# pcb_univ_3-_1-3-5_-x-x-rev5.net
KiCad netlist of a schematic drawn in EAGLE
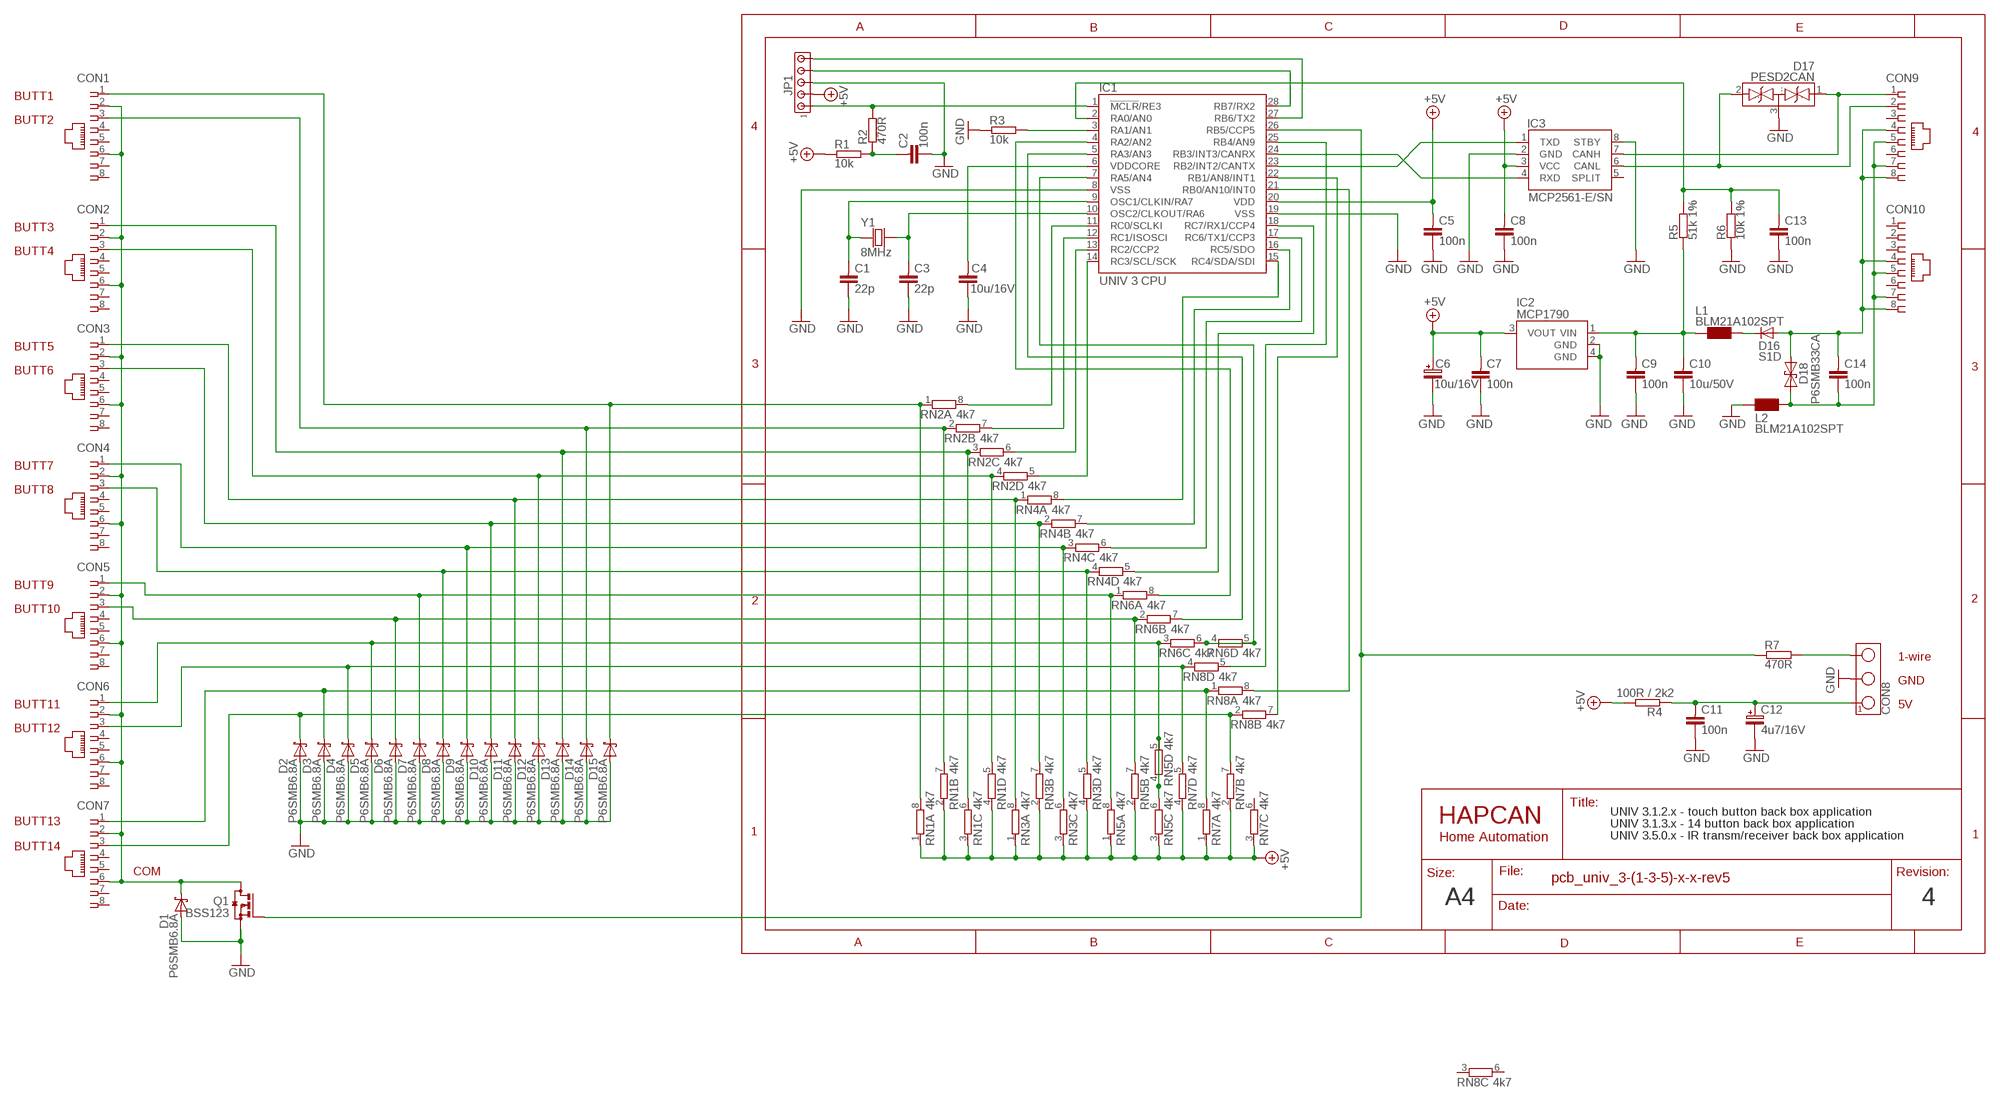
[diagram p0: schematic, sheet 1]

(export (version "E")
  (design (tool "Eeschema 10.0.6"))
  (components
    (comp (ref "C1")
      (value "22p")
      (footprint "eagle-import:0805")
      (libsource (lib "eagle-import") (part "CAPACITOR0805"))
    )
    (comp (ref "C2")
      (value "100n")
      (footprint "eagle-import:0805")
      (libsource (lib "eagle-import") (part "CAPACITOR0805"))
    )
    (comp (ref "C3")
      (value "22p")
      (footprint "eagle-import:0805")
      (libsource (lib "eagle-import") (part "CAPACITOR0805"))
    )
    (comp (ref "C4")
      (value "10u/16V")
      (footprint "eagle-import:0805")
      (libsource (lib "eagle-import") (part "CAPACITOR0805"))
    )
    (comp (ref "C5")
      (value "100n")
      (footprint "eagle-import:0805")
      (libsource (lib "eagle-import") (part "CAPACITOR0805"))
    )
    (comp (ref "C6")
      (value "10u/16V")
      (footprint "eagle-import:SMC_B")
      (libsource (lib "eagle-import") (part "CAPACITOR-POLARIZED-SMC_B"))
    )
    (comp (ref "C7")
      (value "100n")
      (footprint "eagle-import:0805")
      (libsource (lib "eagle-import") (part "CAPACITOR0805"))
    )
    (comp (ref "C8")
      (value "100n")
      (footprint "eagle-import:0805")
      (libsource (lib "eagle-import") (part "CAPACITOR0805"))
    )
    (comp (ref "C9")
      (value "100n")
      (footprint "eagle-import:0805")
      (libsource (lib "eagle-import") (part "CAPACITOR0805"))
    )
    (comp (ref "C10")
      (value "10u/50V")
      (footprint "eagle-import:1210")
      (libsource (lib "eagle-import") (part "CAPACITOR1210"))
    )
    (comp (ref "C11")
      (value "100n")
      (footprint "eagle-import:0805")
      (libsource (lib "eagle-import") (part "CAPACITOR0805"))
    )
    (comp (ref "C12")
      (value "4u7/16V")
      (footprint "eagle-import:SMC_B")
      (libsource (lib "eagle-import") (part "CAPACITOR-POLARIZED-SMC_B"))
    )
    (comp (ref "C13")
      (value "100n")
      (footprint "eagle-import:0805")
      (libsource (lib "eagle-import") (part "CAPACITOR0805"))
    )
    (comp (ref "C14")
      (value "100n")
      (footprint "eagle-import:0805")
      (libsource (lib "eagle-import") (part "CAPACITOR0805"))
    )
    (comp (ref "CON1")
      (value "RJ45-SOCKET")
      (footprint "eagle-import:RJ45-PCB-SOCKET")
      (libsource (lib "eagle-import") (part "RJ45-SOCKET"))
    )
    (comp (ref "CON2")
      (value "RJ45-SOCKET")
      (footprint "eagle-import:RJ45-PCB-SOCKET")
      (libsource (lib "eagle-import") (part "RJ45-SOCKET"))
    )
    (comp (ref "CON3")
      (value "RJ45-SOCKET")
      (footprint "eagle-import:RJ45-PCB-SOCKET")
      (libsource (lib "eagle-import") (part "RJ45-SOCKET"))
    )
    (comp (ref "CON4")
      (value "RJ45-SOCKET")
      (footprint "eagle-import:RJ45-PCB-SOCKET")
      (libsource (lib "eagle-import") (part "RJ45-SOCKET"))
    )
    (comp (ref "CON5")
      (value "RJ45-SOCKET")
      (footprint "eagle-import:RJ45-PCB-SOCKET")
      (libsource (lib "eagle-import") (part "RJ45-SOCKET"))
    )
    (comp (ref "CON6")
      (value "RJ45-SOCKET")
      (footprint "eagle-import:RJ45-PCB-SOCKET")
      (libsource (lib "eagle-import") (part "RJ45-SOCKET"))
    )
    (comp (ref "CON7")
      (value "RJ45-SOCKET")
      (footprint "eagle-import:RJ45-PCB-SOCKET")
      (libsource (lib "eagle-import") (part "RJ45-SOCKET"))
    )
    (comp (ref "CON8")
      (value "TERMINAL-3")
      (footprint "eagle-import:ARK3-5X10.5MM")
      (libsource (lib "eagle-import") (part "TERMINAL-3-5X10.5MM"))
    )
    (comp (ref "CON9")
      (value "RJ45-SOCKET")
      (footprint "eagle-import:RJ45-PCB-SOCKET")
      (libsource (lib "eagle-import") (part "RJ45-SOCKET"))
    )
    (comp (ref "CON10")
      (value "RJ45-SOCKET")
      (footprint "eagle-import:RJ45-PCB-SOCKET")
      (libsource (lib "eagle-import") (part "RJ45-SOCKET"))
    )
    (comp (ref "D1")
      (value "P6SMB6.8A")
      (footprint "eagle-import:DO-214")
      (libsource (lib "eagle-import") (part "DIODE_TRANSIL1_DO214"))
    )
    (comp (ref "D2")
      (value "P6SMB6.8A")
      (footprint "eagle-import:DO-214")
      (libsource (lib "eagle-import") (part "DIODE_TRANSIL1_DO214"))
    )
    (comp (ref "D3")
      (value "P6SMB6.8A")
      (footprint "eagle-import:DO-214")
      (libsource (lib "eagle-import") (part "DIODE_TRANSIL1_DO214"))
    )
    (comp (ref "D4")
      (value "P6SMB6.8A")
      (footprint "eagle-import:DO-214")
      (libsource (lib "eagle-import") (part "DIODE_TRANSIL1_DO214"))
    )
    (comp (ref "D5")
      (value "P6SMB6.8A")
      (footprint "eagle-import:DO-214")
      (libsource (lib "eagle-import") (part "DIODE_TRANSIL1_DO214"))
    )
    (comp (ref "D6")
      (value "P6SMB6.8A")
      (footprint "eagle-import:DO-214")
      (libsource (lib "eagle-import") (part "DIODE_TRANSIL1_DO214"))
    )
    (comp (ref "D7")
      (value "P6SMB6.8A")
      (footprint "eagle-import:DO-214")
      (libsource (lib "eagle-import") (part "DIODE_TRANSIL1_DO214"))
    )
    (comp (ref "D8")
      (value "P6SMB6.8A")
      (footprint "eagle-import:DO-214")
      (libsource (lib "eagle-import") (part "DIODE_TRANSIL1_DO214"))
    )
    (comp (ref "D9")
      (value "P6SMB6.8A")
      (footprint "eagle-import:DO-214")
      (libsource (lib "eagle-import") (part "DIODE_TRANSIL1_DO214"))
    )
    (comp (ref "D10")
      (value "P6SMB6.8A")
      (footprint "eagle-import:DO-214")
      (libsource (lib "eagle-import") (part "DIODE_TRANSIL1_DO214"))
    )
    (comp (ref "D11")
      (value "P6SMB6.8A")
      (footprint "eagle-import:DO-214")
      (libsource (lib "eagle-import") (part "DIODE_TRANSIL1_DO214"))
    )
    (comp (ref "D12")
      (value "P6SMB6.8A")
      (footprint "eagle-import:DO-214")
      (libsource (lib "eagle-import") (part "DIODE_TRANSIL1_DO214"))
    )
    (comp (ref "D13")
      (value "P6SMB6.8A")
      (footprint "eagle-import:DO-214")
      (libsource (lib "eagle-import") (part "DIODE_TRANSIL1_DO214"))
    )
    (comp (ref "D14")
      (value "P6SMB6.8A")
      (footprint "eagle-import:DO-214")
      (libsource (lib "eagle-import") (part "DIODE_TRANSIL1_DO214"))
    )
    (comp (ref "D15")
      (value "P6SMB6.8A")
      (footprint "eagle-import:DO-214")
      (libsource (lib "eagle-import") (part "DIODE_TRANSIL1_DO214"))
    )
    (comp (ref "D16")
      (value "S1D")
      (footprint "eagle-import:DO-214")
      (libsource (lib "eagle-import") (part "DIODE_DO-214"))
    )
    (comp (ref "D17")
      (value "PESD2CAN")
      (footprint "eagle-import:SOT-23")
      (libsource (lib "eagle-import") (part "PESD2CANSOT-23"))
    )
    (comp (ref "D18")
      (value "P6SMB33CA")
      (footprint "eagle-import:DO-214_TRANSIL2")
      (libsource (lib "eagle-import") (part "DIODE_TRANSIL2"))
    )
    (comp (ref "IC1")
      (value "UNIV 3 CPU")
      (footprint "eagle-import:UNIV3CPU")
      (libsource (lib "eagle-import") (part "UNIV3CPU-I/SO"))
    )
    (comp (ref "IC2")
      (value "MCP1790")
      (footprint "eagle-import:SOT-223")
      (libsource (lib "eagle-import") (part "MCP1790"))
    )
    (comp (ref "IC3")
      (value "MCP2561-E/SN")
      (footprint "eagle-import:SO-08")
      (libsource (lib "eagle-import") (part "MCP2561-E/SN"))
    )
    (comp (ref "JP1")
      (value "HEADER5")
      (footprint "eagle-import:SIP-5")
      (libsource (lib "eagle-import") (part "HEADER5"))
    )
    (comp (ref "L1")
      (value "BLM21A102SPT")
      (footprint "eagle-import:0805@1")
      (libsource (lib "eagle-import") (part "BLMXXX"))
    )
    (comp (ref "L2")
      (value "BLM21A102SPT")
      (footprint "eagle-import:0805@1")
      (libsource (lib "eagle-import") (part "BLMXXX"))
    )
    (comp (ref "Q1")
      (value "BSS123")
      (footprint "eagle-import:SOT23")
      (libsource (lib "eagle-import") (part "BSS123"))
    )
    (comp (ref "R1")
      (value "10k")
      (footprint "eagle-import:0805")
      (libsource (lib "eagle-import") (part "RESISTOR0805"))
    )
    (comp (ref "R2")
      (value "470R")
      (footprint "eagle-import:0805")
      (libsource (lib "eagle-import") (part "RESISTOR0805"))
    )
    (comp (ref "R3")
      (value "10k")
      (footprint "eagle-import:0805")
      (libsource (lib "eagle-import") (part "RESISTOR0805"))
    )
    (comp (ref "R4")
      (value "100R / 2k2")
      (footprint "eagle-import:0805")
      (libsource (lib "eagle-import") (part "RESISTOR0805"))
    )
    (comp (ref "R5")
      (value "51k 1%")
      (footprint "eagle-import:0805")
      (libsource (lib "eagle-import") (part "RESISTOR0805"))
    )
    (comp (ref "R6")
      (value "10k 1%")
      (footprint "eagle-import:0805")
      (libsource (lib "eagle-import") (part "RESISTOR0805"))
    )
    (comp (ref "R7")
      (value "470R")
      (footprint "eagle-import:0805")
      (libsource (lib "eagle-import") (part "RESISTOR0805"))
    )
    (comp (ref "RN1")
      (value "4k7")
      (footprint "eagle-import:EXB38V")
      (libsource (lib "eagle-import") (part "4R-NEXB38V"))
    )
    (comp (ref "RN2")
      (value "4k7")
      (footprint "eagle-import:EXB38V")
      (libsource (lib "eagle-import") (part "4R-NEXB38V"))
    )
    (comp (ref "RN3")
      (value "4k7")
      (footprint "eagle-import:EXB38V")
      (libsource (lib "eagle-import") (part "4R-NEXB38V"))
    )
    (comp (ref "RN4")
      (value "4k7")
      (footprint "eagle-import:EXB38V")
      (libsource (lib "eagle-import") (part "4R-NEXB38V"))
    )
    (comp (ref "RN5")
      (value "4k7")
      (footprint "eagle-import:EXB38V")
      (libsource (lib "eagle-import") (part "4R-NEXB38V"))
    )
    (comp (ref "RN6")
      (value "4k7")
      (footprint "eagle-import:EXB38V")
      (libsource (lib "eagle-import") (part "4R-NEXB38V"))
    )
    (comp (ref "RN7")
      (value "4k7")
      (footprint "eagle-import:EXB38V")
      (libsource (lib "eagle-import") (part "4R-NEXB38V"))
    )
    (comp (ref "RN8")
      (value "4k7")
      (footprint "eagle-import:EXB38V")
      (libsource (lib "eagle-import") (part "4R-NEXB38V"))
    )
    (comp (ref "Y1")
      (value "8MHz")
      (footprint "eagle-import:CRYSTAL-HC49V")
      (libsource (lib "eagle-import") (part "CRYSTAL-HC49V"))
    )
  )
  (nets
    (net (code "1") (name "+5V") (class "Default")
      (node (ref "C5") (pin "1") (pinfunction "1_1") (pintype "passive"))
      (node (ref "C6") (pin "+") (pinfunction "1_+") (pintype "passive"))
      (node (ref "C7") (pin "1") (pinfunction "1_1") (pintype "passive"))
      (node (ref "C8") (pin "1") (pinfunction "1_1") (pintype "passive"))
      (node (ref "IC1") (pin "20") (pinfunction "VDD_20") (pintype "bidirectional"))
      (node (ref "IC2") (pin "3") (pinfunction "VOUT_3") (pintype "bidirectional"))
      (node (ref "IC3") (pin "3") (pinfunction "VCC_3") (pintype "bidirectional"))
      (node (ref "JP1") (pin "2") (pinfunction "2_2") (pintype "passive"))
      (node (ref "R1") (pin "1") (pinfunction "1_1") (pintype "passive"))
      (node (ref "R4") (pin "1") (pinfunction "1_1") (pintype "passive"))
      (node (ref "RN1") (pin "1") (pinfunction "1_1") (pintype "passive"))
      (node (ref "RN1") (pin "2") (pinfunction "1_2") (pintype "passive"))
      (node (ref "RN1") (pin "3") (pinfunction "1_3") (pintype "passive"))
      (node (ref "RN1") (pin "4") (pinfunction "1_4") (pintype "passive"))
      (node (ref "RN3") (pin "1") (pinfunction "1_1") (pintype "passive"))
      (node (ref "RN3") (pin "2") (pinfunction "1_2") (pintype "passive"))
      (node (ref "RN3") (pin "3") (pinfunction "1_3") (pintype "passive"))
      (node (ref "RN3") (pin "4") (pinfunction "1_4") (pintype "passive"))
      (node (ref "RN5") (pin "1") (pinfunction "1_1") (pintype "passive"))
      (node (ref "RN5") (pin "2") (pinfunction "1_2") (pintype "passive"))
      (node (ref "RN5") (pin "3") (pinfunction "1_3") (pintype "passive"))
      (node (ref "RN7") (pin "1") (pinfunction "1_1") (pintype "passive"))
      (node (ref "RN7") (pin "2") (pinfunction "1_2") (pintype "passive"))
      (node (ref "RN7") (pin "3") (pinfunction "1_3") (pintype "passive"))
      (node (ref "RN7") (pin "4") (pinfunction "1_4") (pintype "passive"))
    )
    (net (code "2") (name "GND") (class "Default")
      (node (ref "C1") (pin "2") (pinfunction "2_2") (pintype "passive"))
      (node (ref "C10") (pin "2") (pinfunction "2_2") (pintype "passive"))
      (node (ref "C11") (pin "2") (pinfunction "2_2") (pintype "passive"))
      (node (ref "C12") (pin "-") (pinfunction "2_-") (pintype "passive"))
      (node (ref "C13") (pin "2") (pinfunction "2_2") (pintype "passive"))
      (node (ref "C2") (pin "2") (pinfunction "2_2") (pintype "passive"))
      (node (ref "C3") (pin "2") (pinfunction "2_2") (pintype "passive"))
      (node (ref "C4") (pin "2") (pinfunction "2_2") (pintype "passive"))
      (node (ref "C5") (pin "2") (pinfunction "2_2") (pintype "passive"))
      (node (ref "C6") (pin "-") (pinfunction "2_-") (pintype "passive"))
      (node (ref "C7") (pin "2") (pinfunction "2_2") (pintype "passive"))
      (node (ref "C8") (pin "2") (pinfunction "2_2") (pintype "passive"))
      (node (ref "C9") (pin "2") (pinfunction "2_2") (pintype "passive"))
      (node (ref "CON8") (pin "2") (pinfunction "2_2") (pintype "passive"))
      (node (ref "D1") (pin "A") (pinfunction "A_A") (pintype "passive"))
      (node (ref "D10") (pin "A") (pinfunction "A_A") (pintype "passive"))
      (node (ref "D11") (pin "A") (pinfunction "A_A") (pintype "passive"))
      (node (ref "D12") (pin "A") (pinfunction "A_A") (pintype "passive"))
      (node (ref "D13") (pin "A") (pinfunction "A_A") (pintype "passive"))
      (node (ref "D14") (pin "A") (pinfunction "A_A") (pintype "passive"))
      (node (ref "D15") (pin "A") (pinfunction "A_A") (pintype "passive"))
      (node (ref "D17") (pin "3") (pinfunction "..._3") (pintype "bidirectional"))
      (node (ref "D2") (pin "A") (pinfunction "A_A") (pintype "passive"))
      (node (ref "D3") (pin "A") (pinfunction "A_A") (pintype "passive"))
      (node (ref "D4") (pin "A") (pinfunction "A_A") (pintype "passive"))
      (node (ref "D5") (pin "A") (pinfunction "A_A") (pintype "passive"))
      (node (ref "D6") (pin "A") (pinfunction "A_A") (pintype "passive"))
      (node (ref "D7") (pin "A") (pinfunction "A_A") (pintype "passive"))
      (node (ref "D8") (pin "A") (pinfunction "A_A") (pintype "passive"))
      (node (ref "D9") (pin "A") (pinfunction "A_A") (pintype "passive"))
      (node (ref "IC1") (pin "19") (pinfunction "VSS_19") (pintype "bidirectional"))
      (node (ref "IC1") (pin "8") (pinfunction "VSS_8") (pintype "bidirectional"))
      (node (ref "IC2") (pin "2") (pinfunction "GND_2") (pintype "bidirectional"))
      (node (ref "IC2") (pin "4") (pinfunction "GND_4") (pintype "bidirectional"))
      (node (ref "IC3") (pin "2") (pinfunction "GND_2") (pintype "bidirectional"))
      (node (ref "IC3") (pin "8") (pinfunction "STBY_8") (pintype "bidirectional"))
      (node (ref "JP1") (pin "3") (pinfunction "3_3") (pintype "passive"))
      (node (ref "L2") (pin "1") (pinfunction "1_1") (pintype "passive"))
      (node (ref "Q1") (pin "2") (pinfunction "S_2") (pintype "passive"))
      (node (ref "R3") (pin "1") (pinfunction "1_1") (pintype "passive"))
      (node (ref "R6") (pin "1") (pinfunction "1_1") (pintype "passive"))
    )
    (net (code "3") (name "Net-(C2-Pad1)") (class "Default")
      (node (ref "C2") (pin "1") (pinfunction "1_1") (pintype "passive"))
      (node (ref "R1") (pin "2") (pinfunction "2_2") (pintype "passive"))
      (node (ref "R2") (pin "1") (pinfunction "1_1") (pintype "passive"))
    )
    (net (code "4") (name "Net-(C12-1)") (class "Default")
      (node (ref "C11") (pin "1") (pinfunction "1_1") (pintype "passive"))
      (node (ref "C12") (pin "+") (pinfunction "1_+") (pintype "passive"))
      (node (ref "CON8") (pin "1") (pinfunction "1_1") (pintype "passive"))
      (node (ref "R4") (pin "2") (pinfunction "2_2") (pintype "passive"))
    )
    (net (code "5") (name "Net-(CON8-Pad3)") (class "Default")
      (node (ref "CON8") (pin "3") (pinfunction "3_3") (pintype "passive"))
      (node (ref "R7") (pin "2") (pinfunction "2_2") (pintype "passive"))
    )
    (net (code "6") (name "Net-(D16-PadC)") (class "Default")
      (node (ref "D16") (pin "C") (pinfunction "C_C") (pintype "passive"))
      (node (ref "L1") (pin "2") (pinfunction "2_2") (pintype "passive"))
    )
    (net (code "7") (name "Net-(D17-.)") (class "Default")
      (node (ref "CON9") (pin "1") (pinfunction "1_1") (pintype "passive"))
      (node (ref "D17") (pin "1") (pinfunction "._1") (pintype "bidirectional"))
      (node (ref "IC3") (pin "7") (pinfunction "CANH_7") (pintype "bidirectional"))
    )
    (net (code "8") (name "Net-(D17-..)") (class "Default")
      (node (ref "CON9") (pin "2") (pinfunction "2_2") (pintype "passive"))
      (node (ref "D17") (pin "2") (pinfunction ".._2") (pintype "bidirectional"))
      (node (ref "IC3") (pin "6") (pinfunction "CANL_6") (pintype "bidirectional"))
    )
    (net (code "9") (name "Net-(D18-1)") (class "Default")
      (node (ref "C14") (pin "1") (pinfunction "1_1") (pintype "passive"))
      (node (ref "CON10") (pin "4") (pinfunction "4_4") (pintype "passive"))
      (node (ref "CON10") (pin "8") (pinfunction "8_8") (pintype "passive"))
      (node (ref "CON9") (pin "4") (pinfunction "4_4") (pintype "passive"))
      (node (ref "CON9") (pin "8") (pinfunction "8_8") (pintype "passive"))
      (node (ref "D16") (pin "A") (pinfunction "A_A") (pintype "passive"))
      (node (ref "D18") (pin "A") (pinfunction "1_A") (pintype "passive"))
    )
    (net (code "10") (name "Net-(D18-2)") (class "Default")
      (node (ref "C14") (pin "2") (pinfunction "2_2") (pintype "passive"))
      (node (ref "CON10") (pin "5") (pinfunction "5_5") (pintype "passive"))
      (node (ref "CON10") (pin "7") (pinfunction "7_7") (pintype "passive"))
      (node (ref "CON9") (pin "5") (pinfunction "5_5") (pintype "passive"))
      (node (ref "CON9") (pin "7") (pinfunction "7_7") (pintype "passive"))
      (node (ref "D18") (pin "C") (pinfunction "2_C") (pintype "passive"))
      (node (ref "L2") (pin "2") (pinfunction "2_2") (pintype "passive"))
    )
    (net (code "11") (name "Net-(IC1-OSC1{slash}CLKIN{slash}RA7)") (class "Default")
      (node (ref "C1") (pin "1") (pinfunction "1_1") (pintype "passive"))
      (node (ref "IC1") (pin "9") (pinfunction "OSC1/CLKIN/RA7_9") (pintype "bidirectional"))
      (node (ref "Y1") (pin "1") (pinfunction "1_1") (pintype "passive"))
    )
    (net (code "12") (name "Net-(IC1-OSC2{slash}CLKOUT{slash}RA6)") (class "Default")
      (node (ref "C3") (pin "1") (pinfunction "1_1") (pintype "passive"))
      (node (ref "IC1") (pin "10") (pinfunction "OSC2/CLKOUT/RA6_10") (pintype "bidirectional"))
      (node (ref "Y1") (pin "2") (pinfunction "2_2") (pintype "passive"))
    )
    (net (code "13") (name "Net-(IC1-RA0{slash}AN0)") (class "Default")
      (node (ref "C13") (pin "1") (pinfunction "1_1") (pintype "passive"))
      (node (ref "IC1") (pin "2") (pinfunction "RA0/AN0_2") (pintype "bidirectional"))
      (node (ref "R5") (pin "2") (pinfunction "2_2") (pintype "passive"))
      (node (ref "R6") (pin "2") (pinfunction "2_2") (pintype "passive"))
    )
    (net (code "14") (name "Net-(IC1-RA1{slash}AN1)") (class "Default")
      (node (ref "IC1") (pin "3") (pinfunction "RA1/AN1_3") (pintype "bidirectional"))
      (node (ref "R3") (pin "2") (pinfunction "2_2") (pintype "passive"))
    )
    (net (code "15") (name "Net-(IC1-RA2{slash}AN2)") (class "Default")
      (node (ref "IC1") (pin "4") (pinfunction "RA2/AN2_4") (pintype "bidirectional"))
      (node (ref "RN6") (pin "8") (pinfunction "2_8") (pintype "passive"))
    )
    (net (code "16") (name "Net-(IC1-RA3{slash}AN3)") (class "Default")
      (node (ref "IC1") (pin "5") (pinfunction "RA3/AN3_5") (pintype "bidirectional"))
      (node (ref "RN6") (pin "7") (pinfunction "2_7") (pintype "passive"))
    )
    (net (code "17") (name "Net-(IC1-RA5{slash}AN4)") (class "Default")
      (node (ref "IC1") (pin "7") (pinfunction "RA5/AN4_7") (pintype "bidirectional"))
      (node (ref "RN6") (pin "4") (pinfunction "1_4") (pintype "passive"))
      (node (ref "RN6") (pin "5") (pinfunction "2_5") (pintype "passive"))
      (node (ref "RN6") (pin "6") (pinfunction "2_6") (pintype "passive"))
    )
    (net (code "18") (name "Net-(IC1-RB0{slash}AN10{slash}INT0)") (class "Default")
      (node (ref "IC1") (pin "21") (pinfunction "RB0/AN10/INT0_21") (pintype "bidirectional"))
      (node (ref "RN8") (pin "8") (pinfunction "2_8") (pintype "passive"))
    )
    (net (code "19") (name "Net-(IC1-RB1{slash}AN8{slash}INT1)") (class "Default")
      (node (ref "IC1") (pin "22") (pinfunction "RB1/AN8/INT1_22") (pintype "bidirectional"))
      (node (ref "RN8") (pin "7") (pinfunction "2_7") (pintype "passive"))
    )
    (net (code "20") (name "Net-(IC1-RB2{slash}INT2{slash}CANTX)") (class "Default")
      (node (ref "IC1") (pin "23") (pinfunction "RB2/INT2/CANTX_23") (pintype "bidirectional"))
      (node (ref "IC3") (pin "1") (pinfunction "TXD_1") (pintype "bidirectional"))
    )
    (net (code "21") (name "Net-(IC1-RB3{slash}INT3{slash}CANRX)") (class "Default")
      (node (ref "IC1") (pin "24") (pinfunction "RB3/INT3/CANRX_24") (pintype "bidirectional"))
      (node (ref "IC3") (pin "4") (pinfunction "RXD_4") (pintype "bidirectional"))
    )
    (net (code "22") (name "Net-(IC1-RB4{slash}AN9)") (class "Default")
      (node (ref "IC1") (pin "25") (pinfunction "RB4/AN9_25") (pintype "bidirectional"))
      (node (ref "RN8") (pin "5") (pinfunction "2_5") (pintype "passive"))
    )
    (net (code "23") (name "Net-(IC1-RB5{slash}CCP5)") (class "Default")
      (node (ref "IC1") (pin "26") (pinfunction "RB5/CCP5_26") (pintype "bidirectional"))
      (node (ref "Q1") (pin "1") (pinfunction "G_1") (pintype "passive"))
      (node (ref "R7") (pin "1") (pinfunction "1_1") (pintype "passive"))
    )
    (net (code "24") (name "Net-(IC1-RB6{slash}TX2)") (class "Default")
      (node (ref "IC1") (pin "27") (pinfunction "RB6/TX2_27") (pintype "bidirectional"))
      (node (ref "JP1") (pin "5") (pinfunction "5_5") (pintype "passive"))
    )
    (net (code "25") (name "Net-(IC1-RB7{slash}RX2)") (class "Default")
      (node (ref "IC1") (pin "28") (pinfunction "RB7/RX2_28") (pintype "bidirectional"))
      (node (ref "JP1") (pin "4") (pinfunction "4_4") (pintype "passive"))
    )
    (net (code "26") (name "Net-(IC1-RC0{slash}SCLKI)") (class "Default")
      (node (ref "IC1") (pin "11") (pinfunction "RC0/SCLKI_11") (pintype "bidirectional"))
      (node (ref "RN2") (pin "8") (pinfunction "2_8") (pintype "passive"))
    )
    (net (code "27") (name "Net-(IC1-RC1{slash}ISOSCI)") (class "Default")
      (node (ref "IC1") (pin "12") (pinfunction "RC1/ISOSCI_12") (pintype "bidirectional"))
      (node (ref "RN2") (pin "7") (pinfunction "2_7") (pintype "passive"))
    )
    (net (code "28") (name "Net-(IC1-RC2{slash}CCP2)") (class "Default")
      (node (ref "IC1") (pin "13") (pinfunction "RC2/CCP2_13") (pintype "bidirectional"))
      (node (ref "RN2") (pin "6") (pinfunction "2_6") (pintype "passive"))
    )
    (net (code "29") (name "Net-(IC1-RC3{slash}SCL{slash}SCK)") (class "Default")
      (node (ref "IC1") (pin "14") (pinfunction "RC3/SCL/SCK_14") (pintype "bidirectional"))
      (node (ref "RN2") (pin "5") (pinfunction "2_5") (pintype "passive"))
    )
    (net (code "30") (name "Net-(IC1-RC4{slash}SDA{slash}SDI)") (class "Default")
      (node (ref "IC1") (pin "15") (pinfunction "RC4/SDA/SDI_15") (pintype "bidirectional"))
      (node (ref "RN4") (pin "8") (pinfunction "2_8") (pintype "passive"))
    )
    (net (code "31") (name "Net-(IC1-RC5{slash}SDO)") (class "Default")
      (node (ref "IC1") (pin "16") (pinfunction "RC5/SDO_16") (pintype "bidirectional"))
      (node (ref "RN4") (pin "7") (pinfunction "2_7") (pintype "passive"))
    )
    (net (code "32") (name "Net-(IC1-RC6{slash}TX1{slash}CCP3)") (class "Default")
      (node (ref "IC1") (pin "17") (pinfunction "RC6/TX1/CCP3_17") (pintype "bidirectional"))
      (node (ref "RN4") (pin "6") (pinfunction "2_6") (pintype "passive"))
    )
    (net (code "33") (name "Net-(IC1-RC7{slash}RX1{slash}CCP4)") (class "Default")
      (node (ref "IC1") (pin "18") (pinfunction "RC7/RX1/CCP4_18") (pintype "bidirectional"))
      (node (ref "RN4") (pin "5") (pinfunction "2_5") (pintype "passive"))
    )
    (net (code "34") (name "Net-(IC1-VDDCORE)") (class "Default")
      (node (ref "C4") (pin "1") (pinfunction "1_1") (pintype "passive"))
      (node (ref "IC1") (pin "6") (pinfunction "VDDCORE_6") (pintype "bidirectional"))
    )
    (net (code "35") (name "Net-(IC1-~{MCLR}{slash}RE3)") (class "Default")
      (node (ref "IC1") (pin "1") (pinfunction "~{MCLR}/RE3_1") (pintype "bidirectional"))
      (node (ref "JP1") (pin "1") (pinfunction "1_1") (pintype "passive"))
      (node (ref "R2") (pin "2") (pinfunction "2_2") (pintype "passive"))
    )
    (net (code "36") (name "Net-(IC2-VIN)") (class "Default")
      (node (ref "C10") (pin "1") (pinfunction "1_1") (pintype "passive"))
      (node (ref "C9") (pin "1") (pinfunction "1_1") (pintype "passive"))
      (node (ref "IC2") (pin "1") (pinfunction "VIN_1") (pintype "bidirectional"))
      (node (ref "L1") (pin "1") (pinfunction "1_1") (pintype "passive"))
      (node (ref "R5") (pin "1") (pinfunction "1_1") (pintype "passive"))
    )
    (net (code "37") (name "Net-(Q1-D)") (class "Default")
      (node (ref "CON1") (pin "2") (pinfunction "2_2") (pintype "passive"))
      (node (ref "CON1") (pin "6") (pinfunction "6_6") (pintype "passive"))
      (node (ref "CON2") (pin "2") (pinfunction "2_2") (pintype "passive"))
      (node (ref "CON2") (pin "6") (pinfunction "6_6") (pintype "passive"))
      (node (ref "CON3") (pin "2") (pinfunction "2_2") (pintype "passive"))
      (node (ref "CON3") (pin "6") (pinfunction "6_6") (pintype "passive"))
      (node (ref "CON4") (pin "2") (pinfunction "2_2") (pintype "passive"))
      (node (ref "CON4") (pin "6") (pinfunction "6_6") (pintype "passive"))
      (node (ref "CON5") (pin "2") (pinfunction "2_2") (pintype "passive"))
      (node (ref "CON5") (pin "6") (pinfunction "6_6") (pintype "passive"))
      (node (ref "CON6") (pin "2") (pinfunction "2_2") (pintype "passive"))
      (node (ref "CON6") (pin "6") (pinfunction "6_6") (pintype "passive"))
      (node (ref "CON7") (pin "2") (pinfunction "2_2") (pintype "passive"))
      (node (ref "CON7") (pin "6") (pinfunction "6_6") (pintype "passive"))
      (node (ref "D1") (pin "C") (pinfunction "C_C") (pintype "passive"))
      (node (ref "Q1") (pin "3") (pinfunction "D_3") (pintype "passive"))
    )
    (net (code "38") (name "Net-(RN1A-2)") (class "Default")
      (node (ref "CON1") (pin "1") (pinfunction "1_1") (pintype "passive"))
      (node (ref "D15") (pin "C") (pinfunction "C_C") (pintype "passive"))
      (node (ref "RN1") (pin "8") (pinfunction "2_8") (pintype "passive"))
      (node (ref "RN2") (pin "1") (pinfunction "1_1") (pintype "passive"))
    )
    (net (code "39") (name "Net-(RN1B-2)") (class "Default")
      (node (ref "CON1") (pin "3") (pinfunction "3_3") (pintype "passive"))
      (node (ref "D14") (pin "C") (pinfunction "C_C") (pintype "passive"))
      (node (ref "RN1") (pin "7") (pinfunction "2_7") (pintype "passive"))
      (node (ref "RN2") (pin "2") (pinfunction "1_2") (pintype "passive"))
    )
    (net (code "40") (name "Net-(RN1C-2)") (class "Default")
      (node (ref "CON2") (pin "1") (pinfunction "1_1") (pintype "passive"))
      (node (ref "D13") (pin "C") (pinfunction "C_C") (pintype "passive"))
      (node (ref "RN1") (pin "6") (pinfunction "2_6") (pintype "passive"))
      (node (ref "RN2") (pin "3") (pinfunction "1_3") (pintype "passive"))
    )
    (net (code "41") (name "Net-(RN1D-2)") (class "Default")
      (node (ref "CON2") (pin "3") (pinfunction "3_3") (pintype "passive"))
      (node (ref "D12") (pin "C") (pinfunction "C_C") (pintype "passive"))
      (node (ref "RN1") (pin "5") (pinfunction "2_5") (pintype "passive"))
      (node (ref "RN2") (pin "4") (pinfunction "1_4") (pintype "passive"))
    )
    (net (code "42") (name "Net-(RN3A-2)") (class "Default")
      (node (ref "CON3") (pin "1") (pinfunction "1_1") (pintype "passive"))
      (node (ref "D11") (pin "C") (pinfunction "C_C") (pintype "passive"))
      (node (ref "RN3") (pin "8") (pinfunction "2_8") (pintype "passive"))
      (node (ref "RN4") (pin "1") (pinfunction "1_1") (pintype "passive"))
    )
    (net (code "43") (name "Net-(RN3B-2)") (class "Default")
      (node (ref "CON3") (pin "3") (pinfunction "3_3") (pintype "passive"))
      (node (ref "D10") (pin "C") (pinfunction "C_C") (pintype "passive"))
      (node (ref "RN3") (pin "7") (pinfunction "2_7") (pintype "passive"))
      (node (ref "RN4") (pin "2") (pinfunction "1_2") (pintype "passive"))
    )
    (net (code "44") (name "Net-(RN3C-2)") (class "Default")
      (node (ref "CON4") (pin "1") (pinfunction "1_1") (pintype "passive"))
      (node (ref "D9") (pin "C") (pinfunction "C_C") (pintype "passive"))
      (node (ref "RN3") (pin "6") (pinfunction "2_6") (pintype "passive"))
      (node (ref "RN4") (pin "3") (pinfunction "1_3") (pintype "passive"))
    )
    (net (code "45") (name "Net-(RN3D-2)") (class "Default")
      (node (ref "CON4") (pin "3") (pinfunction "3_3") (pintype "passive"))
      (node (ref "D8") (pin "C") (pinfunction "C_C") (pintype "passive"))
      (node (ref "RN3") (pin "5") (pinfunction "2_5") (pintype "passive"))
      (node (ref "RN4") (pin "4") (pinfunction "1_4") (pintype "passive"))
    )
    (net (code "46") (name "Net-(RN5A-2)") (class "Default")
      (node (ref "CON5") (pin "1") (pinfunction "1_1") (pintype "passive"))
      (node (ref "D7") (pin "C") (pinfunction "C_C") (pintype "passive"))
      (node (ref "RN5") (pin "8") (pinfunction "2_8") (pintype "passive"))
      (node (ref "RN6") (pin "1") (pinfunction "1_1") (pintype "passive"))
    )
    (net (code "47") (name "Net-(RN5B-2)") (class "Default")
      (node (ref "CON5") (pin "3") (pinfunction "3_3") (pintype "passive"))
      (node (ref "D6") (pin "C") (pinfunction "C_C") (pintype "passive"))
      (node (ref "RN5") (pin "7") (pinfunction "2_7") (pintype "passive"))
      (node (ref "RN6") (pin "2") (pinfunction "1_2") (pintype "passive"))
    )
    (net (code "48") (name "Net-(RN5C-2)") (class "Default")
      (node (ref "CON6") (pin "1") (pinfunction "1_1") (pintype "passive"))
      (node (ref "D5") (pin "C") (pinfunction "C_C") (pintype "passive"))
      (node (ref "RN5") (pin "4") (pinfunction "1_4") (pintype "passive"))
      (node (ref "RN5") (pin "5") (pinfunction "2_5") (pintype "passive"))
      (node (ref "RN5") (pin "6") (pinfunction "2_6") (pintype "passive"))
      (node (ref "RN6") (pin "3") (pinfunction "1_3") (pintype "passive"))
    )
    (net (code "49") (name "Net-(RN7A-2)") (class "Default")
      (node (ref "CON7") (pin "1") (pinfunction "1_1") (pintype "passive"))
      (node (ref "D3") (pin "C") (pinfunction "C_C") (pintype "passive"))
      (node (ref "RN7") (pin "8") (pinfunction "2_8") (pintype "passive"))
      (node (ref "RN8") (pin "1") (pinfunction "1_1") (pintype "passive"))
    )
    (net (code "50") (name "Net-(RN7B-2)") (class "Default")
      (node (ref "CON7") (pin "3") (pinfunction "3_3") (pintype "passive"))
      (node (ref "D2") (pin "C") (pinfunction "C_C") (pintype "passive"))
      (node (ref "RN7") (pin "7") (pinfunction "2_7") (pintype "passive"))
      (node (ref "RN8") (pin "2") (pinfunction "1_2") (pintype "passive"))
    )
    (net (code "51") (name "Net-(RN7D-2)") (class "Default")
      (node (ref "CON6") (pin "3") (pinfunction "3_3") (pintype "passive"))
      (node (ref "D4") (pin "C") (pinfunction "C_C") (pintype "passive"))
      (node (ref "RN7") (pin "5") (pinfunction "2_5") (pintype "passive"))
      (node (ref "RN8") (pin "4") (pinfunction "1_4") (pintype "passive"))
    )
    (net (code "52") (name "unconnected-(CON1-Pad4)") (class "Default")
      (node (ref "CON1") (pin "4") (pinfunction "4_4") (pintype "passive"))
    )
    (net (code "53") (name "unconnected-(CON1-Pad5)") (class "Default")
      (node (ref "CON1") (pin "5") (pinfunction "5_5") (pintype "passive"))
    )
    (net (code "54") (name "unconnected-(CON1-Pad7)") (class "Default")
      (node (ref "CON1") (pin "7") (pinfunction "7_7") (pintype "passive"))
    )
    (net (code "55") (name "unconnected-(CON1-Pad8)") (class "Default")
      (node (ref "CON1") (pin "8") (pinfunction "8_8") (pintype "passive"))
    )
    (net (code "56") (name "unconnected-(CON2-Pad4)") (class "Default")
      (node (ref "CON2") (pin "4") (pinfunction "4_4") (pintype "passive"))
    )
    (net (code "57") (name "unconnected-(CON2-Pad5)") (class "Default")
      (node (ref "CON2") (pin "5") (pinfunction "5_5") (pintype "passive"))
    )
    (net (code "58") (name "unconnected-(CON2-Pad7)") (class "Default")
      (node (ref "CON2") (pin "7") (pinfunction "7_7") (pintype "passive"))
    )
    (net (code "59") (name "unconnected-(CON2-Pad8)") (class "Default")
      (node (ref "CON2") (pin "8") (pinfunction "8_8") (pintype "passive"))
    )
    (net (code "60") (name "unconnected-(CON3-Pad4)") (class "Default")
      (node (ref "CON3") (pin "4") (pinfunction "4_4") (pintype "passive"))
    )
    (net (code "61") (name "unconnected-(CON3-Pad5)") (class "Default")
      (node (ref "CON3") (pin "5") (pinfunction "5_5") (pintype "passive"))
    )
    (net (code "62") (name "unconnected-(CON3-Pad7)") (class "Default")
      (node (ref "CON3") (pin "7") (pinfunction "7_7") (pintype "passive"))
    )
    (net (code "63") (name "unconnected-(CON3-Pad8)") (class "Default")
      (node (ref "CON3") (pin "8") (pinfunction "8_8") (pintype "passive"))
    )
    (net (code "64") (name "unconnected-(CON4-Pad4)") (class "Default")
      (node (ref "CON4") (pin "4") (pinfunction "4_4") (pintype "passive"))
    )
    (net (code "65") (name "unconnected-(CON4-Pad5)") (class "Default")
      (node (ref "CON4") (pin "5") (pinfunction "5_5") (pintype "passive"))
    )
    (net (code "66") (name "unconnected-(CON4-Pad7)") (class "Default")
      (node (ref "CON4") (pin "7") (pinfunction "7_7") (pintype "passive"))
    )
    (net (code "67") (name "unconnected-(CON4-Pad8)") (class "Default")
      (node (ref "CON4") (pin "8") (pinfunction "8_8") (pintype "passive"))
    )
    (net (code "68") (name "unconnected-(CON5-Pad4)") (class "Default")
      (node (ref "CON5") (pin "4") (pinfunction "4_4") (pintype "passive"))
    )
    (net (code "69") (name "unconnected-(CON5-Pad5)") (class "Default")
      (node (ref "CON5") (pin "5") (pinfunction "5_5") (pintype "passive"))
    )
    (net (code "70") (name "unconnected-(CON5-Pad7)") (class "Default")
      (node (ref "CON5") (pin "7") (pinfunction "7_7") (pintype "passive"))
    )
    (net (code "71") (name "unconnected-(CON5-Pad8)") (class "Default")
      (node (ref "CON5") (pin "8") (pinfunction "8_8") (pintype "passive"))
    )
    (net (code "72") (name "unconnected-(CON6-Pad4)") (class "Default")
      (node (ref "CON6") (pin "4") (pinfunction "4_4") (pintype "passive"))
    )
    (net (code "73") (name "unconnected-(CON6-Pad5)") (class "Default")
      (node (ref "CON6") (pin "5") (pinfunction "5_5") (pintype "passive"))
    )
    (net (code "74") (name "unconnected-(CON6-Pad7)") (class "Default")
      (node (ref "CON6") (pin "7") (pinfunction "7_7") (pintype "passive"))
    )
    (net (code "75") (name "unconnected-(CON6-Pad8)") (class "Default")
      (node (ref "CON6") (pin "8") (pinfunction "8_8") (pintype "passive"))
    )
    (net (code "76") (name "unconnected-(CON7-Pad4)") (class "Default")
      (node (ref "CON7") (pin "4") (pinfunction "4_4") (pintype "passive"))
    )
    (net (code "77") (name "unconnected-(CON7-Pad5)") (class "Default")
      (node (ref "CON7") (pin "5") (pinfunction "5_5") (pintype "passive"))
    )
    (net (code "78") (name "unconnected-(CON7-Pad7)") (class "Default")
      (node (ref "CON7") (pin "7") (pinfunction "7_7") (pintype "passive"))
    )
    (net (code "79") (name "unconnected-(CON7-Pad8)") (class "Default")
      (node (ref "CON7") (pin "8") (pinfunction "8_8") (pintype "passive"))
    )
    (net (code "80") (name "unconnected-(CON9-Pad3)") (class "Default")
      (node (ref "CON9") (pin "3") (pinfunction "3_3") (pintype "passive"))
    )
    (net (code "81") (name "unconnected-(CON9-Pad6)") (class "Default")
      (node (ref "CON9") (pin "6") (pinfunction "6_6") (pintype "passive"))
    )
    (net (code "82") (name "unconnected-(CON10-Pad1)") (class "Default")
      (node (ref "CON10") (pin "1") (pinfunction "1_1") (pintype "passive"))
    )
    (net (code "83") (name "unconnected-(CON10-Pad2)") (class "Default")
      (node (ref "CON10") (pin "2") (pinfunction "2_2") (pintype "passive"))
    )
    (net (code "84") (name "unconnected-(CON10-Pad3)") (class "Default")
      (node (ref "CON10") (pin "3") (pinfunction "3_3") (pintype "passive"))
    )
    (net (code "85") (name "unconnected-(CON10-Pad6)") (class "Default")
      (node (ref "CON10") (pin "6") (pinfunction "6_6") (pintype "passive"))
    )
    (net (code "86") (name "unconnected-(IC3-SPLIT-Pad5)") (class "Default")
      (node (ref "IC3") (pin "5") (pinfunction "SPLIT_5") (pintype "bidirectional"))
    )
    (net (code "87") (name "unconnected-(RN7C-2-Pad6)") (class "Default")
      (node (ref "RN7") (pin "6") (pinfunction "2_6") (pintype "passive"))
    )
    (net (code "88") (name "unconnected-(RN8C-1-Pad3)") (class "Default")
      (node (ref "RN8") (pin "3") (pinfunction "1_3") (pintype "passive"))
    )
    (net (code "89") (name "unconnected-(RN8C-2-Pad6)") (class "Default")
      (node (ref "RN8") (pin "6") (pinfunction "2_6") (pintype "passive"))
    )
  )
)
